# LDR_Circuit.net
KiCad netlist of a schematic drawn in EasyEDA
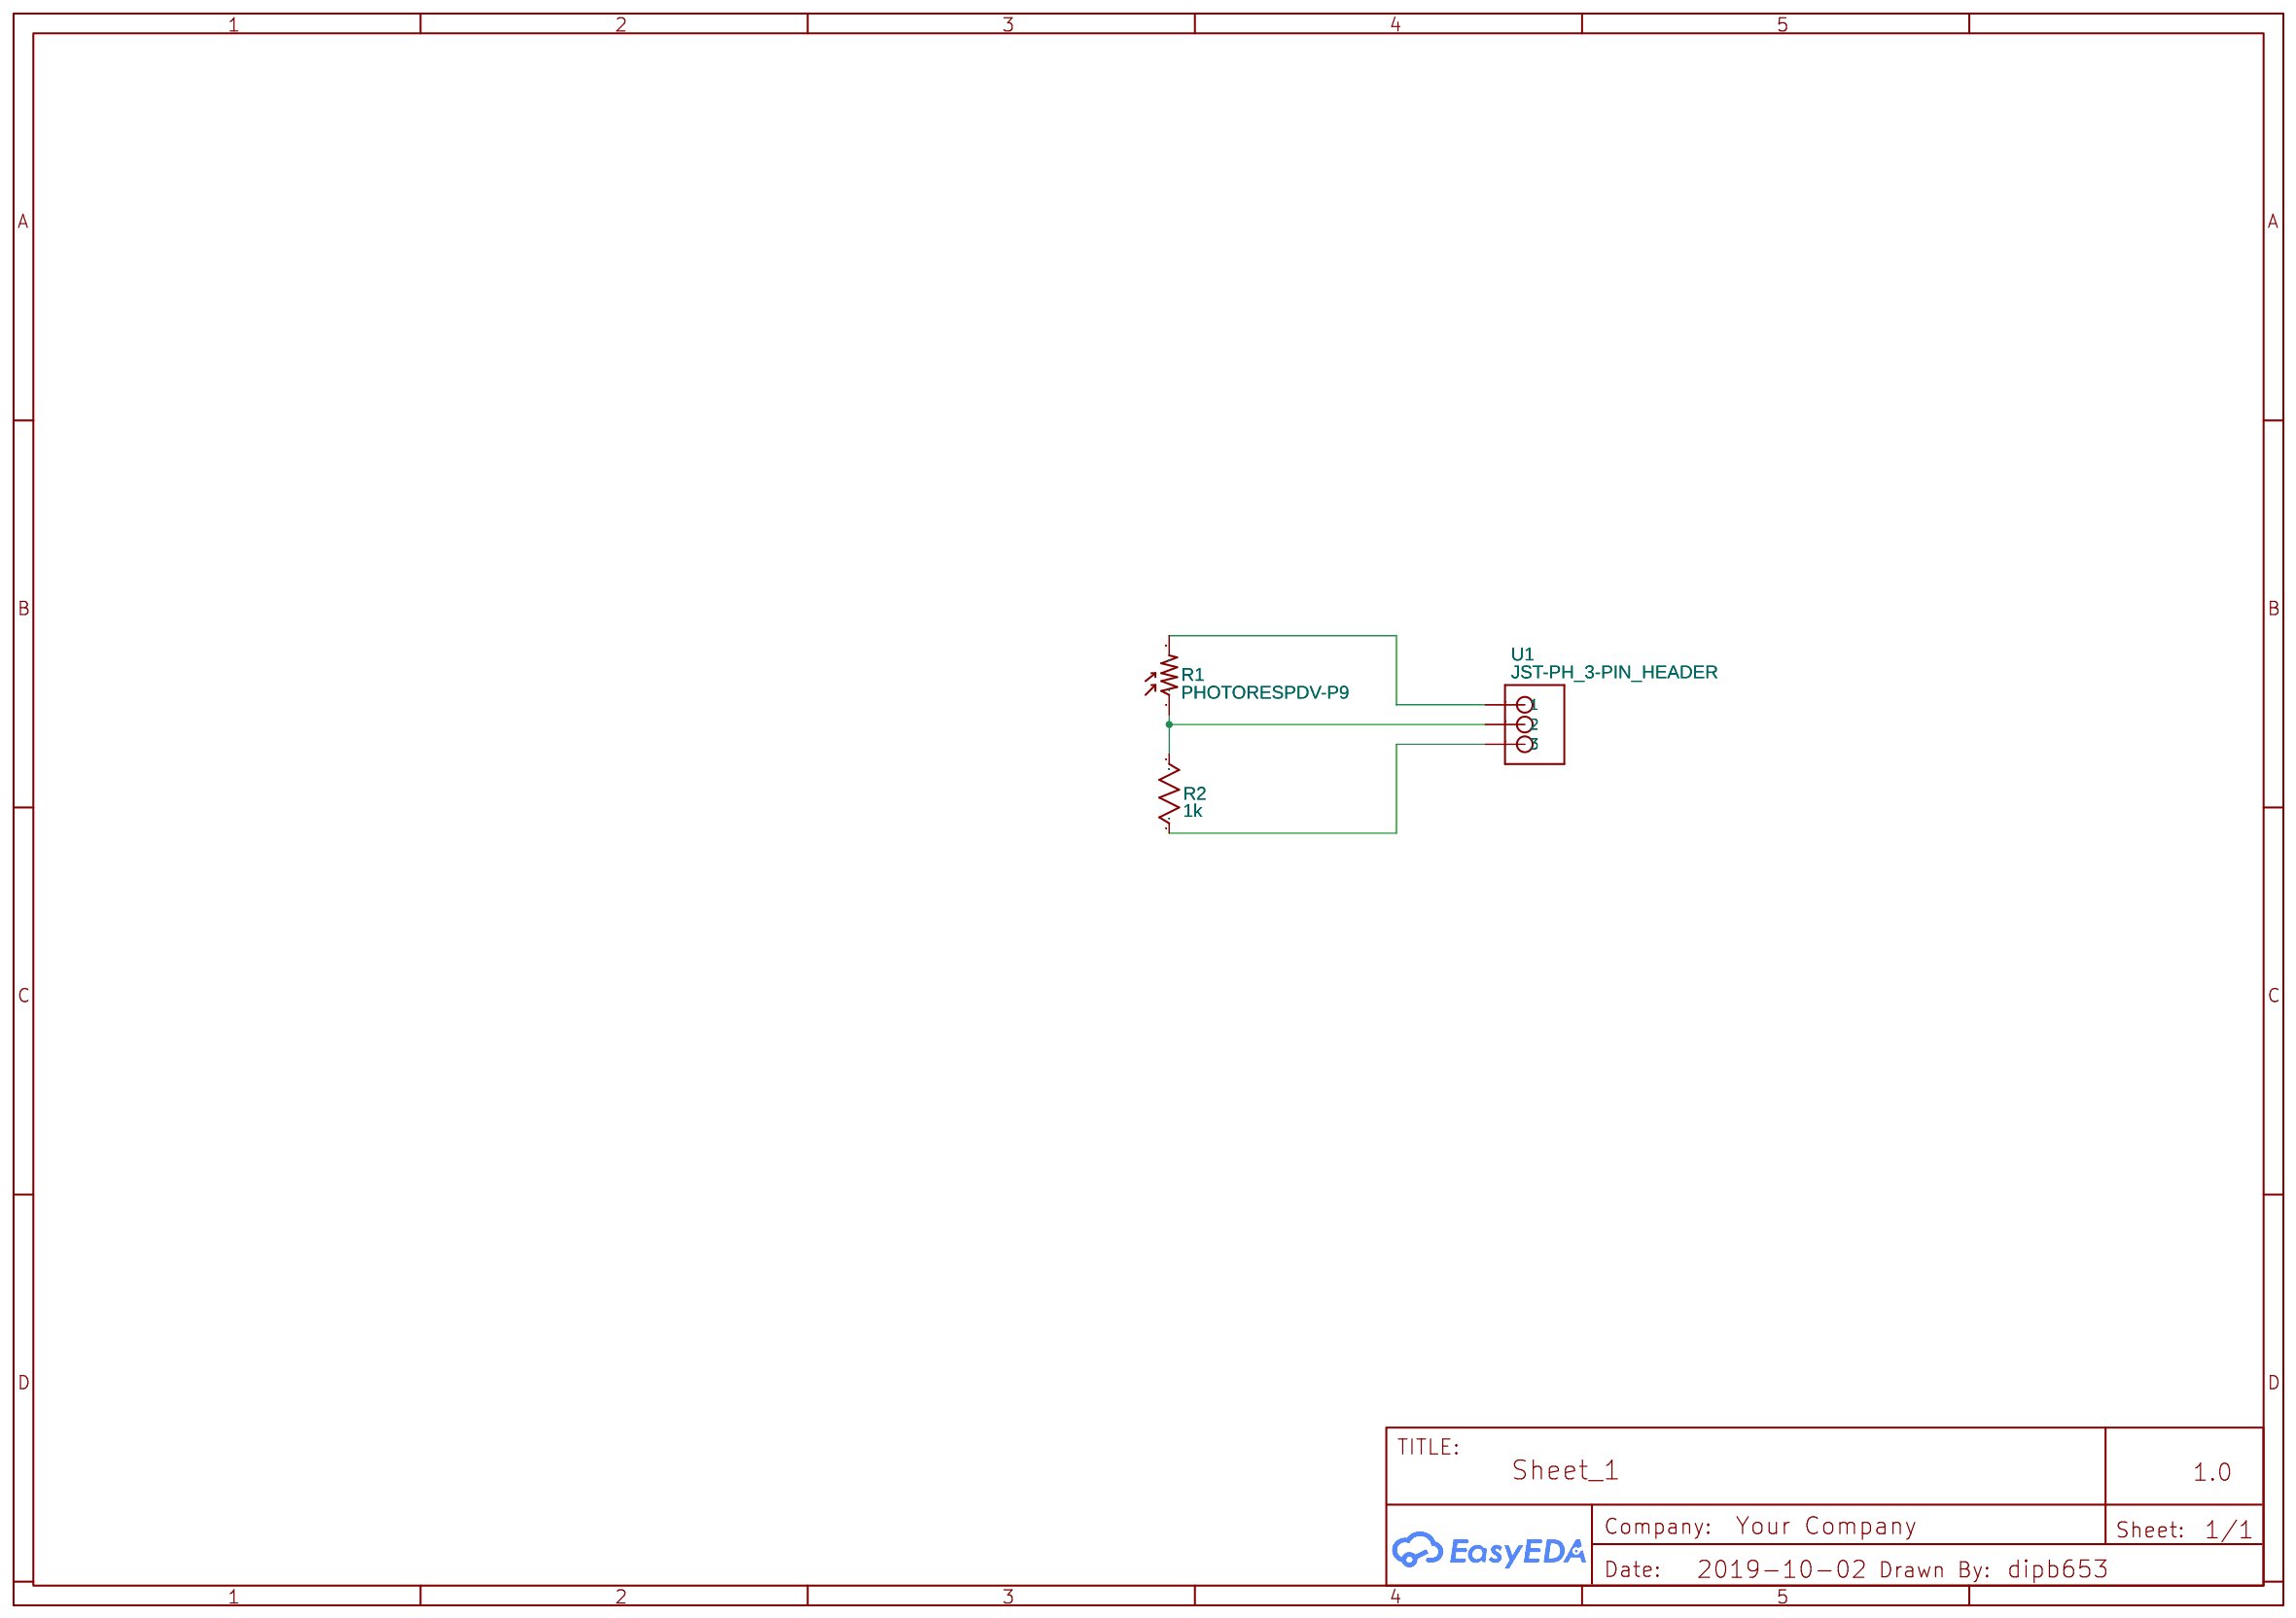
[diagram p0: schematic sheet]

(export (version "E")
  (design (tool "Eeschema 10.0.6"))
  (components
    (comp (ref "R1") (value "PHOTORESPDV-P9") (libsource (lib "") (part "Unknown_580_335")))
    (comp (ref "R2") (value "1k") (libsource (lib "") (part "Res_AXIAL-0.3(1/8W)_US")))
    (comp (ref "U1") (value "JST-PH_3-PIN_HEADER") (libsource (lib "") (part "Unknown_765_360")))
  )
  (nets
    (net (code "1") (name "Net-(U1-1)") (class "Default")
      (node (ref "R1") (pin "2") (pinfunction "2_2") (pintype "unspecified"))
      (node (ref "U1") (pin "P1") (pinfunction "1_P1") (pintype "unspecified"))
    )
    (net (code "2") (name "Net-(U1-2)") (class "Default")
      (node (ref "R1") (pin "1") (pinfunction "1_1") (pintype "unspecified"))
      (node (ref "R2") (pin "2") (pinfunction "2_2") (pintype "unspecified"))
      (node (ref "U1") (pin "P2") (pinfunction "2_P2") (pintype "unspecified"))
    )
    (net (code "3") (name "Net-(U1-3)") (class "Default")
      (node (ref "R2") (pin "1") (pinfunction "1_1") (pintype "unspecified"))
      (node (ref "U1") (pin "P3") (pinfunction "3_P3") (pintype "unspecified"))
    )
  )
)
